# SensadoCalibradoMaquinas.net
KiCad netlist of a schematic drawn in EAGLE
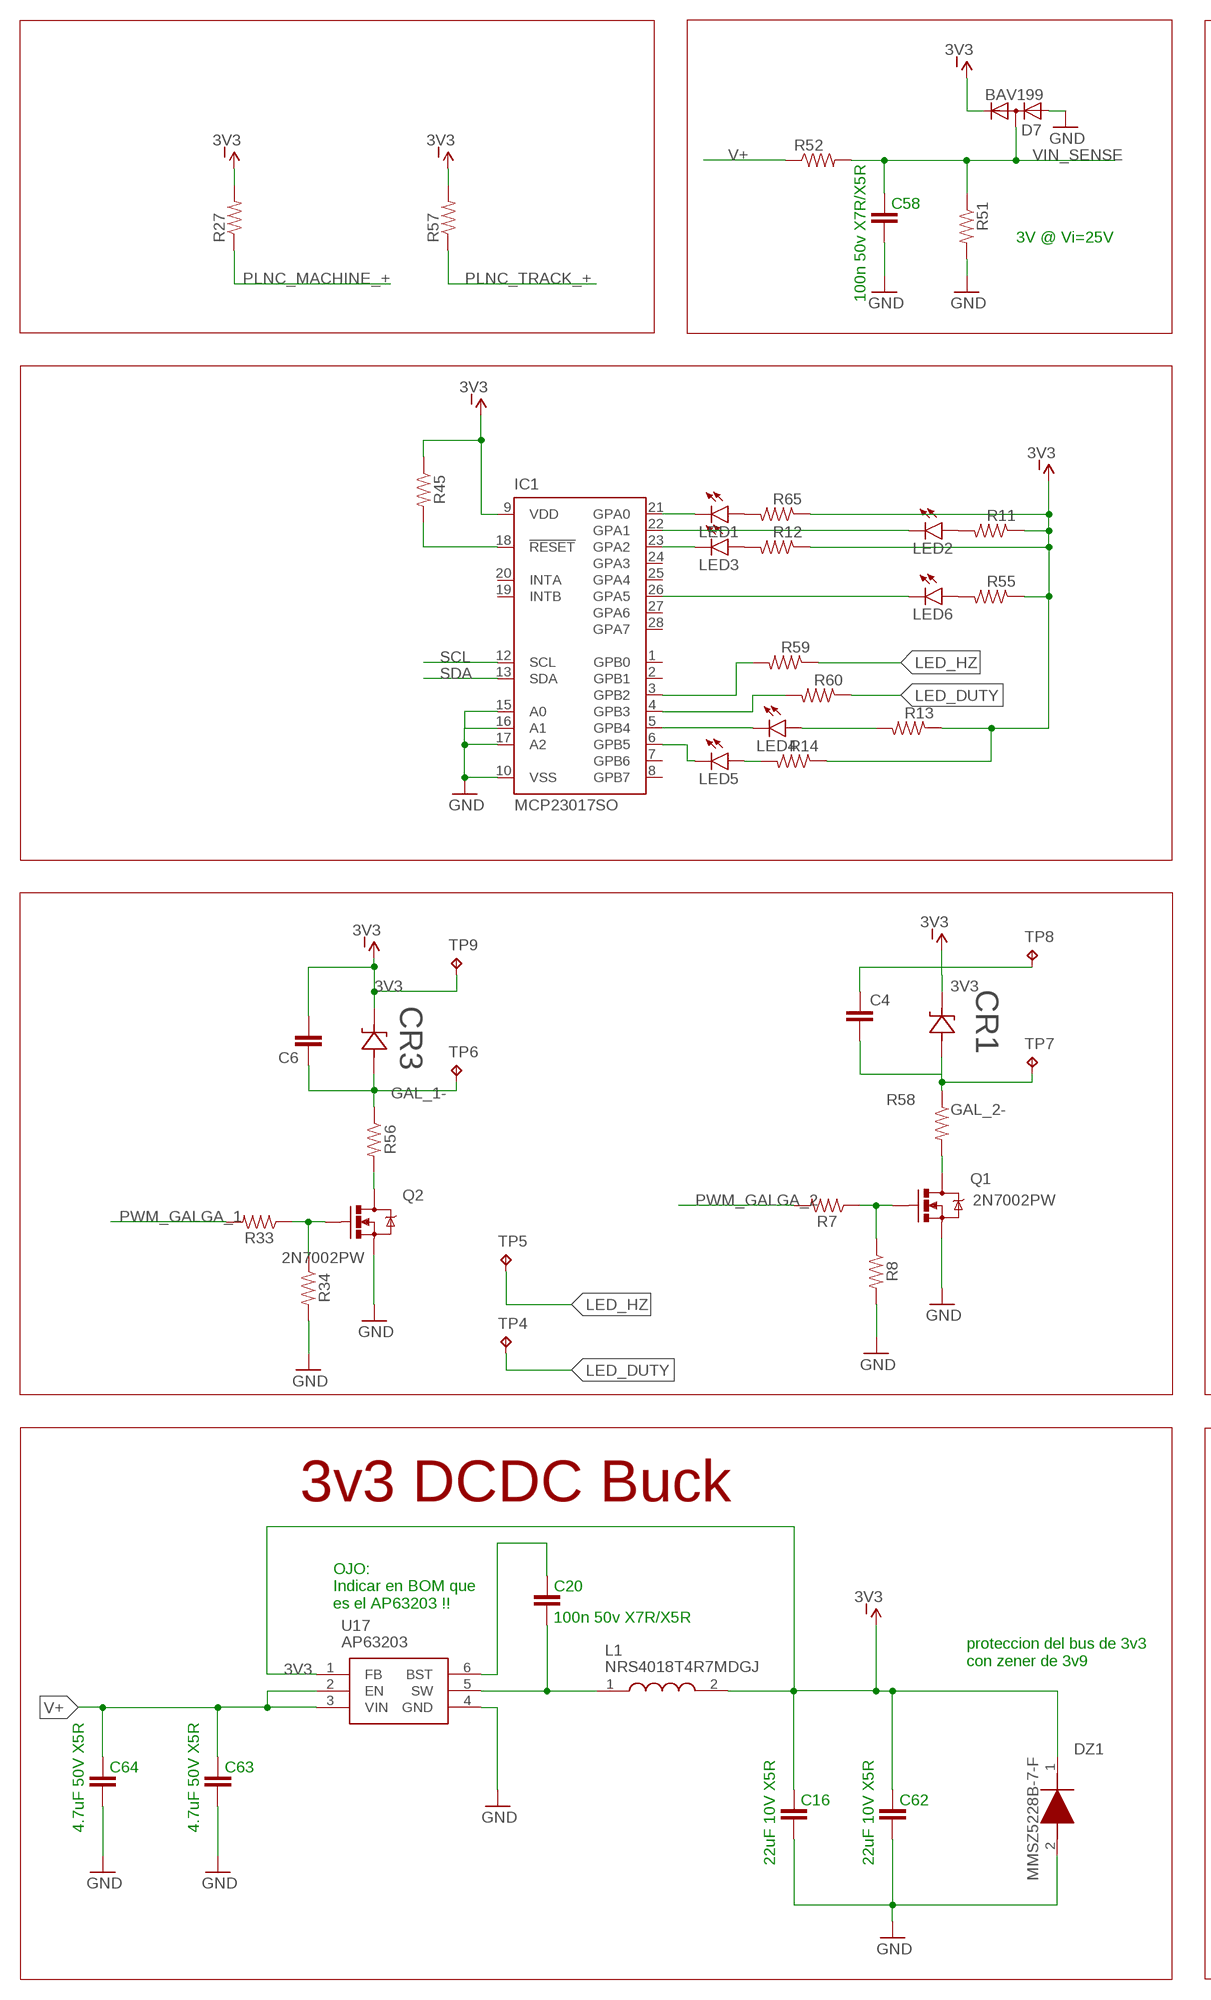
[diagram p0: schematic, sheet 1, part 1 of 2]
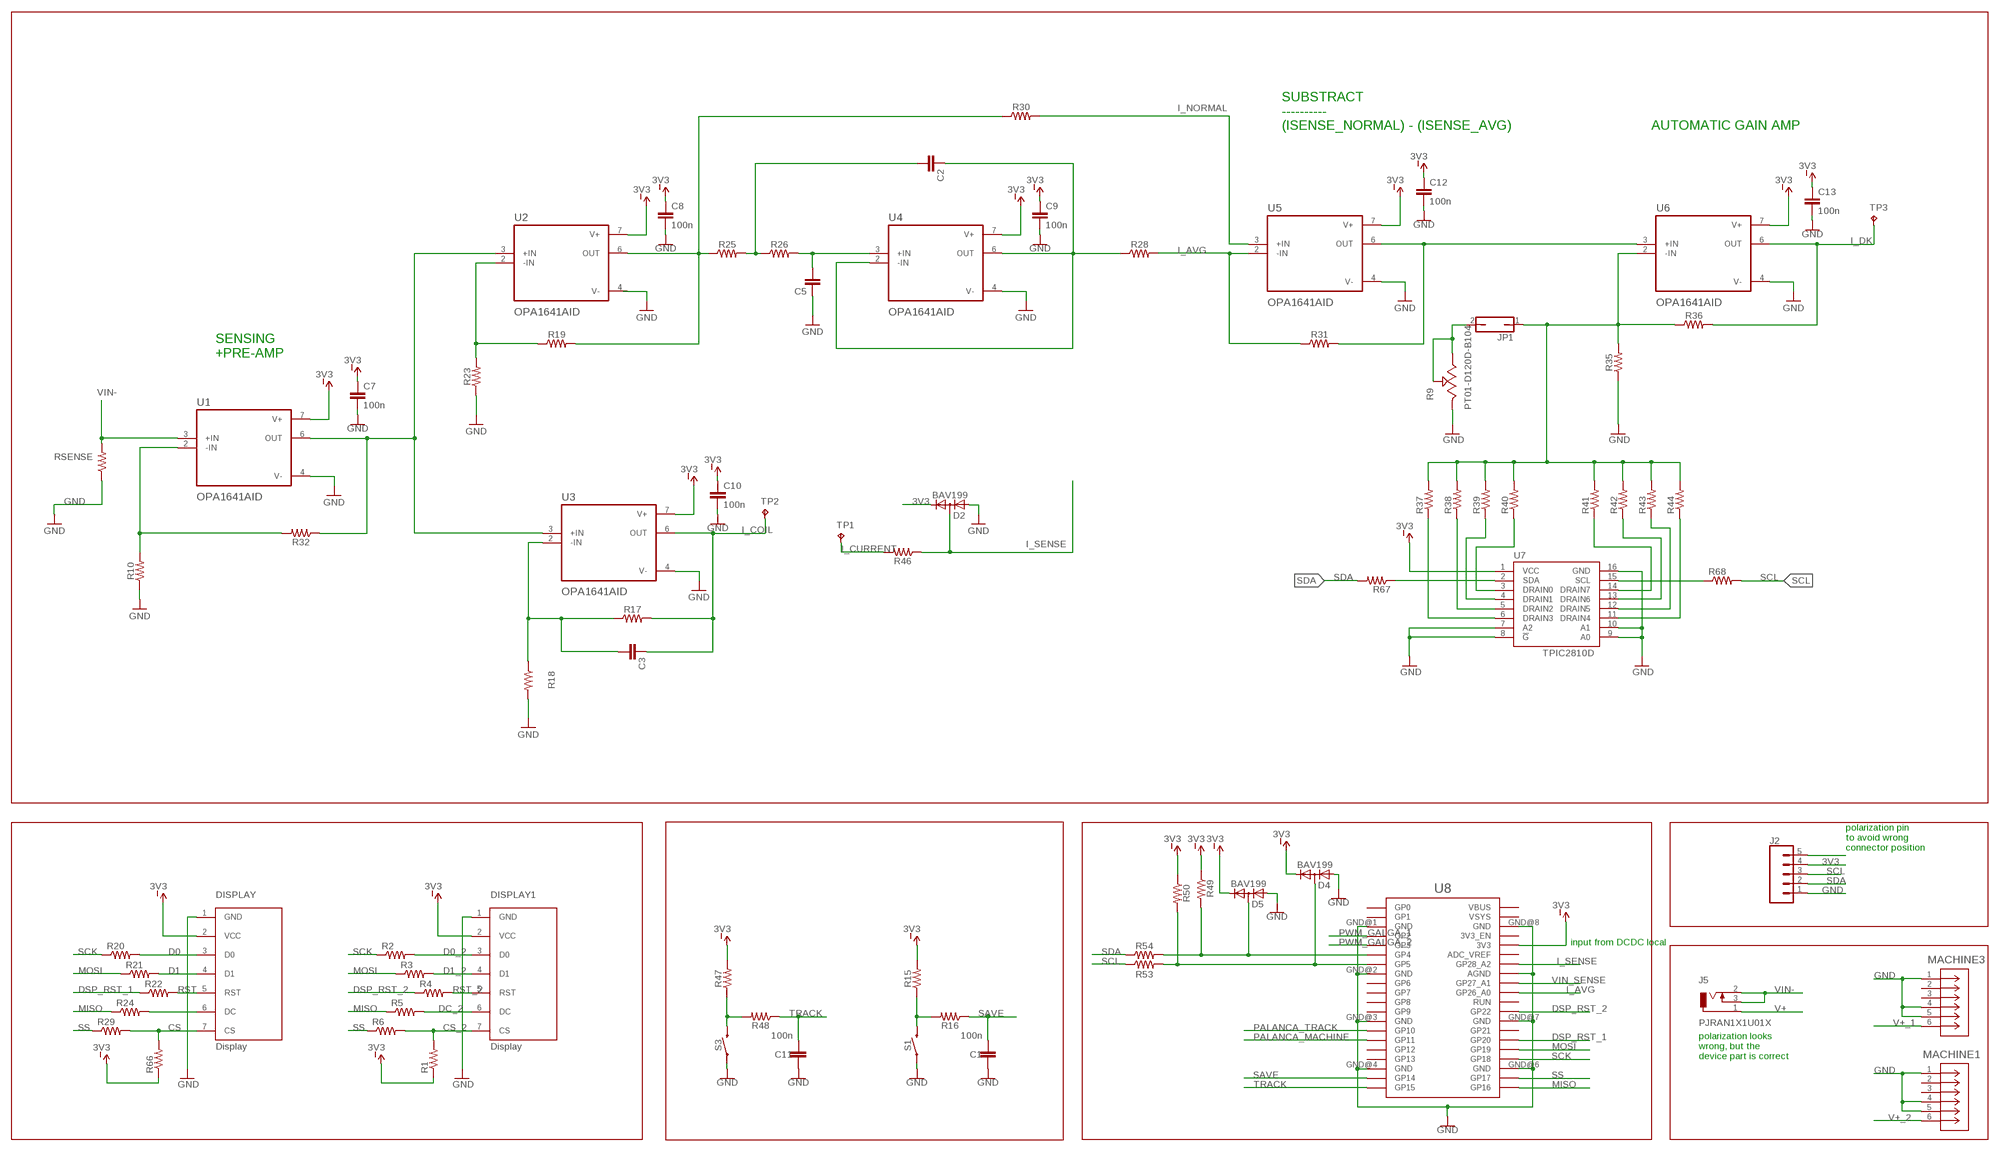
[diagram p1: schematic, sheet 1, part 2 of 2]

(export (version "E")
  (design (tool "Eeschema 10.0.6"))
  (components
    (comp (ref "C1")
      (value "100n")
      (footprint "eagle-import:0805")
      (libsource (lib "eagle-import") (part "1.0UF-0805-25V-(+80/-20%)"))
    )
    (comp (ref "C2")
      (value "CAP0805")
      (footprint "eagle-import:0805")
      (libsource (lib "eagle-import") (part "CAP0805"))
    )
    (comp (ref "C3")
      (value "CAP0805")
      (footprint "eagle-import:0805")
      (libsource (lib "eagle-import") (part "CAP0805"))
    )
    (comp (ref "C4")
      (value "CAP0805")
      (footprint "eagle-import:0805")
      (libsource (lib "eagle-import") (part "CAP0805"))
    )
    (comp (ref "C5")
      (value "CAP0805")
      (footprint "eagle-import:0805")
      (libsource (lib "eagle-import") (part "CAP0805"))
    )
    (comp (ref "C6")
      (value "CAP0805")
      (footprint "eagle-import:0805")
      (libsource (lib "eagle-import") (part "CAP0805"))
    )
    (comp (ref "C7")
      (value "100n")
      (footprint "eagle-import:0805")
      (libsource (lib "eagle-import") (part "1.0UF-0805-25V-(+80/-20%)"))
    )
    (comp (ref "C8")
      (value "100n")
      (footprint "eagle-import:0805")
      (libsource (lib "eagle-import") (part "1.0UF-0805-25V-(+80/-20%)"))
    )
    (comp (ref "C9")
      (value "100n")
      (footprint "eagle-import:0805")
      (libsource (lib "eagle-import") (part "1.0UF-0805-25V-(+80/-20%)"))
    )
    (comp (ref "C10")
      (value "100n")
      (footprint "eagle-import:0805")
      (libsource (lib "eagle-import") (part "1.0UF-0805-25V-(+80/-20%)"))
    )
    (comp (ref "C11")
      (value "100n")
      (footprint "eagle-import:0805")
      (libsource (lib "eagle-import") (part "1.0UF-0805-25V-(+80/-20%)"))
    )
    (comp (ref "C12")
      (value "100n")
      (footprint "eagle-import:0805")
      (libsource (lib "eagle-import") (part "1.0UF-0805-25V-(+80/-20%)"))
    )
    (comp (ref "C13")
      (value "100n")
      (footprint "eagle-import:0805")
      (libsource (lib "eagle-import") (part "1.0UF-0805-25V-(+80/-20%)"))
    )
    (comp (ref "C16")
      (value "22uF 10V X5R")
      (footprint "eagle-import:0805")
      (libsource (lib "eagle-import") (part "CAP0805"))
    )
    (comp (ref "C20")
      (value "100n 50v X7R/X5R")
      (footprint "eagle-import:0805")
      (libsource (lib "eagle-import") (part "CAP0805"))
    )
    (comp (ref "C58")
      (value "100n 50v X7R/X5R")
      (footprint "eagle-import:0805")
      (libsource (lib "eagle-import") (part "CAP0805"))
    )
    (comp (ref "C62")
      (value "22uF 10V X5R")
      (footprint "eagle-import:0805")
      (libsource (lib "eagle-import") (part "CAP0805"))
    )
    (comp (ref "C63")
      (value "4.7uF 50V X5R")
      (footprint "eagle-import:0805")
      (libsource (lib "eagle-import") (part "CAP0805"))
    )
    (comp (ref "C64")
      (value "4.7uF 50V X5R")
      (footprint "eagle-import:0805")
      (libsource (lib "eagle-import") (part "CAP0805"))
    )
    (comp (ref "CR1")
      (value "STPS1L40U")
      (footprint "eagle-import:SMB_STM")
      (fields (field (name "COPYRIGHT") "Copyright (C) 2024 Ultra Librarian. All rights reserved."))
      (libsource (lib "eagle-import") (part "STPS1L40U"))
    )
    (comp (ref "CR3")
      (value "STPS1L40U")
      (footprint "eagle-import:SMB_STM")
      (fields (field (name "COPYRIGHT") "Copyright (C) 2024 Ultra Librarian. All rights reserved."))
      (libsource (lib "eagle-import") (part "STPS1L40U"))
    )
    (comp (ref "D2")
      (value "BAV199")
      (footprint "eagle-import:SOT23")
      (libsource (lib "eagle-import") (part "BAV199"))
    )
    (comp (ref "D4")
      (value "BAV199")
      (footprint "eagle-import:SOT23")
      (libsource (lib "eagle-import") (part "BAV199"))
    )
    (comp (ref "D5")
      (value "BAV199")
      (footprint "eagle-import:SOT23")
      (libsource (lib "eagle-import") (part "BAV199"))
    )
    (comp (ref "D7")
      (value "BAV199")
      (footprint "eagle-import:SOT23")
      (libsource (lib "eagle-import") (part "BAV199"))
    )
    (comp (ref "DISPLAY")
      (value "Display")
      (footprint "eagle-import:OLED_LCD")
      (libsource (lib "eagle-import") (part "OLED_LCD"))
    )
    (comp (ref "DISPLAY1")
      (value "Display")
      (footprint "eagle-import:OLED_LCD")
      (libsource (lib "eagle-import") (part "OLED_LCD"))
    )
    (comp (ref "DZ1")
      (value "MMSZ5228B-7-F")
      (footprint "eagle-import:SODFL3518X115N")
      (libsource (lib "eagle-import") (part "MMSZ5228B-7-F"))
    )
    (comp (ref "IC1")
      (value "MCP23017SO")
      (footprint "eagle-import:SO28W")
      (libsource (lib "eagle-import") (part "MCP23017SO"))
    )
    (comp (ref "J2")
      (value "CONN_05")
      (footprint "eagle-import:1X05")
      (libsource (lib "eagle-import") (part "CONN_05"))
    )
    (comp (ref "J5")
      (value "PJRAN1X1U01X")
      (footprint "eagle-import:PJRAN1X1U01X")
      (fields
        (field (name "DIGIKEY_PART_NUMBER") "PJRAN1X1U01X-ND")
        (field (name "MANUFACTURER") "Switchcraft Inc.")
        (field (name "CREATED_BY") "PCBLayout.com")
      )
      (libsource (lib "eagle-import") (part "PJRAN1X1U01X"))
    )
    (comp (ref "JP1")
      (value "JP1Q")
      (footprint "eagle-import:JP1")
      (libsource (lib "eagle-import") (part "JP1Q"))
    )
    (comp (ref "L1")
      (value "NRS4018T4R7MDGJ")
      (footprint "eagle-import:NRS4018T100MDGJ")
      (fields (field (name "MOUSER_PART_NUMBER") "963-NRS4018T4R7MDGJ"))
      (libsource (lib "eagle-import") (part "NRS4018T4R7MDGJ"))
    )
    (comp (ref "LED1")
      (value "LED3MM")
      (footprint "eagle-import:LED3MM")
      (libsource (lib "eagle-import") (part "LED3MM"))
    )
    (comp (ref "LED2")
      (value "LED3MM")
      (footprint "eagle-import:LED3MM")
      (libsource (lib "eagle-import") (part "LED3MM"))
    )
    (comp (ref "LED3")
      (value "LED3MM")
      (footprint "eagle-import:LED3MM")
      (libsource (lib "eagle-import") (part "LED3MM"))
    )
    (comp (ref "LED4")
      (value "LED3MM")
      (footprint "eagle-import:LED3MM")
      (libsource (lib "eagle-import") (part "LED3MM"))
    )
    (comp (ref "LED5")
      (value "LED3MM")
      (footprint "eagle-import:LED3MM")
      (libsource (lib "eagle-import") (part "LED3MM"))
    )
    (comp (ref "LED6")
      (value "LED3MM")
      (footprint "eagle-import:LED3MM")
      (libsource (lib "eagle-import") (part "LED3MM"))
    )
    (comp (ref "MACHINE1")
      (value "ACJS-MHDR")
      (footprint "eagle-import:CONN_MHDR_AMP")
      (fields (field (name "COPYRIGHT") "Copyright (C) 2018 Accelerated Designs. All rights reserved"))
      (libsource (lib "eagle-import") (part "ACJS-MHDR"))
    )
    (comp (ref "MACHINE3")
      (value "ACJS-MHDR")
      (footprint "eagle-import:CONN_MHDR_AMP")
      (fields (field (name "COPYRIGHT") "Copyright (C) 2018 Accelerated Designs. All rights reserved"))
      (libsource (lib "eagle-import") (part "ACJS-MHDR"))
    )
    (comp (ref "Q1")
      (value "2N7002PW")
      (footprint "eagle-import:SOT323")
      (libsource (lib "eagle-import") (part "MOSFET-NCHANNEL2N7002PW"))
    )
    (comp (ref "Q2")
      (value "2N7002PW")
      (footprint "eagle-import:SOT323")
      (libsource (lib "eagle-import") (part "MOSFET-NCHANNEL2N7002PW"))
    )
    (comp (ref "R1")
      (value "RESISTOR0805")
      (footprint "eagle-import:0805")
      (libsource (lib "eagle-import") (part "RESISTOR0805"))
    )
    (comp (ref "R2")
      (value "RESISTOR0805")
      (footprint "eagle-import:0805")
      (libsource (lib "eagle-import") (part "RESISTOR0805"))
    )
    (comp (ref "R3")
      (value "RESISTOR0805")
      (footprint "eagle-import:0805")
      (libsource (lib "eagle-import") (part "RESISTOR0805"))
    )
    (comp (ref "R4")
      (value "RESISTOR0805")
      (footprint "eagle-import:0805")
      (libsource (lib "eagle-import") (part "RESISTOR0805"))
    )
    (comp (ref "R5")
      (value "RESISTOR0805")
      (footprint "eagle-import:0805")
      (libsource (lib "eagle-import") (part "RESISTOR0805"))
    )
    (comp (ref "R6")
      (value "RESISTOR0805")
      (footprint "eagle-import:0805")
      (libsource (lib "eagle-import") (part "RESISTOR0805"))
    )
    (comp (ref "R7")
      (value "RESISTOR0805")
      (footprint "eagle-import:0805")
      (libsource (lib "eagle-import") (part "RESISTOR0805"))
    )
    (comp (ref "R8")
      (value "RESISTOR0805")
      (footprint "eagle-import:0805")
      (libsource (lib "eagle-import") (part "RESISTOR0805"))
    )
    (comp (ref "R9")
      (value "PT01-D120D-B104")
      (footprint "eagle-import:TRIM_PT01-D120D-B104")
      (fields (field (name "MANUFACTURER") "CUI Devices"))
      (libsource (lib "eagle-import") (part "PT01-D120D-B104"))
    )
    (comp (ref "R10")
      (value "RESISTOR0805")
      (footprint "eagle-import:0805")
      (libsource (lib "eagle-import") (part "RESISTOR0805"))
    )
    (comp (ref "R11")
      (value "RESISTOR0805")
      (footprint "eagle-import:0805")
      (libsource (lib "eagle-import") (part "RESISTOR0805"))
    )
    (comp (ref "R12")
      (value "RESISTOR0805")
      (footprint "eagle-import:0805")
      (libsource (lib "eagle-import") (part "RESISTOR0805"))
    )
    (comp (ref "R13")
      (value "RESISTOR0805")
      (footprint "eagle-import:0805")
      (libsource (lib "eagle-import") (part "RESISTOR0805"))
    )
    (comp (ref "R14")
      (value "RESISTOR0805")
      (footprint "eagle-import:0805")
      (libsource (lib "eagle-import") (part "RESISTOR0805"))
    )
    (comp (ref "R15")
      (value "RESISTOR0805")
      (footprint "eagle-import:0805")
      (libsource (lib "eagle-import") (part "RESISTOR0805"))
    )
    (comp (ref "R16")
      (value "RESISTOR0805")
      (footprint "eagle-import:0805")
      (libsource (lib "eagle-import") (part "RESISTOR0805"))
    )
    (comp (ref "R17")
      (value "RESISTOR0805")
      (footprint "eagle-import:0805")
      (libsource (lib "eagle-import") (part "RESISTOR0805"))
    )
    (comp (ref "R18")
      (value "RESISTOR0805")
      (footprint "eagle-import:0805")
      (libsource (lib "eagle-import") (part "RESISTOR0805"))
    )
    (comp (ref "R19")
      (value "RESISTOR0805")
      (footprint "eagle-import:0805")
      (libsource (lib "eagle-import") (part "RESISTOR0805"))
    )
    (comp (ref "R20")
      (value "RESISTOR0805")
      (footprint "eagle-import:0805")
      (libsource (lib "eagle-import") (part "RESISTOR0805"))
    )
    (comp (ref "R21")
      (value "RESISTOR0805")
      (footprint "eagle-import:0805")
      (libsource (lib "eagle-import") (part "RESISTOR0805"))
    )
    (comp (ref "R22")
      (value "RESISTOR0805")
      (footprint "eagle-import:0805")
      (libsource (lib "eagle-import") (part "RESISTOR0805"))
    )
    (comp (ref "R23")
      (value "RESISTOR0805")
      (footprint "eagle-import:0805")
      (libsource (lib "eagle-import") (part "RESISTOR0805"))
    )
    (comp (ref "R24")
      (value "RESISTOR0805")
      (footprint "eagle-import:0805")
      (libsource (lib "eagle-import") (part "RESISTOR0805"))
    )
    (comp (ref "R25")
      (value "RESISTOR0805")
      (footprint "eagle-import:0805")
      (libsource (lib "eagle-import") (part "RESISTOR0805"))
    )
    (comp (ref "R26")
      (value "RESISTOR0805")
      (footprint "eagle-import:0805")
      (libsource (lib "eagle-import") (part "RESISTOR0805"))
    )
    (comp (ref "R27")
      (value "RESISTOR0805")
      (footprint "eagle-import:0805")
      (libsource (lib "eagle-import") (part "RESISTOR0805"))
    )
    (comp (ref "R28")
      (value "RESISTOR0805")
      (footprint "eagle-import:0805")
      (libsource (lib "eagle-import") (part "RESISTOR0805"))
    )
    (comp (ref "R29")
      (value "RESISTOR0805")
      (footprint "eagle-import:0805")
      (libsource (lib "eagle-import") (part "RESISTOR0805"))
    )
    (comp (ref "R30")
      (value "RESISTOR0805")
      (footprint "eagle-import:0805")
      (libsource (lib "eagle-import") (part "RESISTOR0805"))
    )
    (comp (ref "R31")
      (value "RESISTOR0805")
      (footprint "eagle-import:0805")
      (libsource (lib "eagle-import") (part "RESISTOR0805"))
    )
    (comp (ref "R32")
      (value "RESISTOR0805")
      (footprint "eagle-import:0805")
      (libsource (lib "eagle-import") (part "RESISTOR0805"))
    )
    (comp (ref "R33")
      (value "RESISTOR0805")
      (footprint "eagle-import:0805")
      (libsource (lib "eagle-import") (part "RESISTOR0805"))
    )
    (comp (ref "R34")
      (value "RESISTOR0805")
      (footprint "eagle-import:0805")
      (libsource (lib "eagle-import") (part "RESISTOR0805"))
    )
    (comp (ref "R35")
      (value "RESISTOR0805")
      (footprint "eagle-import:0805")
      (libsource (lib "eagle-import") (part "RESISTOR0805"))
    )
    (comp (ref "R36")
      (value "RESISTOR0805")
      (footprint "eagle-import:0805")
      (libsource (lib "eagle-import") (part "RESISTOR0805"))
    )
    (comp (ref "R37")
      (value "RESISTOR0805")
      (footprint "eagle-import:0805")
      (libsource (lib "eagle-import") (part "RESISTOR0805"))
    )
    (comp (ref "R38")
      (value "RESISTOR0805")
      (footprint "eagle-import:0805")
      (libsource (lib "eagle-import") (part "RESISTOR0805"))
    )
    (comp (ref "R39")
      (value "RESISTOR0805")
      (footprint "eagle-import:0805")
      (libsource (lib "eagle-import") (part "RESISTOR0805"))
    )
    (comp (ref "R40")
      (value "RESISTOR0805")
      (footprint "eagle-import:0805")
      (libsource (lib "eagle-import") (part "RESISTOR0805"))
    )
    (comp (ref "R41")
      (value "RESISTOR0805")
      (footprint "eagle-import:0805")
      (libsource (lib "eagle-import") (part "RESISTOR0805"))
    )
    (comp (ref "R42")
      (value "RESISTOR0805")
      (footprint "eagle-import:0805")
      (libsource (lib "eagle-import") (part "RESISTOR0805"))
    )
    (comp (ref "R43")
      (value "RESISTOR0805")
      (footprint "eagle-import:0805")
      (libsource (lib "eagle-import") (part "RESISTOR0805"))
    )
    (comp (ref "R44")
      (value "RESISTOR0805")
      (footprint "eagle-import:0805")
      (libsource (lib "eagle-import") (part "RESISTOR0805"))
    )
    (comp (ref "R45")
      (value "RESISTOR0805")
      (footprint "eagle-import:0805")
      (libsource (lib "eagle-import") (part "RESISTOR0805"))
    )
    (comp (ref "R46")
      (value "RESISTOR0805")
      (footprint "eagle-import:0805")
      (libsource (lib "eagle-import") (part "RESISTOR0805"))
    )
    (comp (ref "R47")
      (value "RESISTOR0805")
      (footprint "eagle-import:0805")
      (libsource (lib "eagle-import") (part "RESISTOR0805"))
    )
    (comp (ref "R48")
      (value "RESISTOR0805")
      (footprint "eagle-import:0805")
      (libsource (lib "eagle-import") (part "RESISTOR0805"))
    )
    (comp (ref "R49")
      (value "RESISTOR0805")
      (footprint "eagle-import:0805")
      (libsource (lib "eagle-import") (part "RESISTOR0805"))
    )
    (comp (ref "R50")
      (value "RESISTOR0805")
      (footprint "eagle-import:0805")
      (libsource (lib "eagle-import") (part "RESISTOR0805"))
    )
    (comp (ref "R51")
      (value "RESISTOR0805")
      (footprint "eagle-import:0805")
      (libsource (lib "eagle-import") (part "RESISTOR0805"))
    )
    (comp (ref "R52")
      (value "RESISTOR0805")
      (footprint "eagle-import:0805")
      (libsource (lib "eagle-import") (part "RESISTOR0805"))
    )
    (comp (ref "R53")
      (value "RESISTOR0805")
      (footprint "eagle-import:0805")
      (libsource (lib "eagle-import") (part "RESISTOR0805"))
    )
    (comp (ref "R54")
      (value "RESISTOR0805")
      (footprint "eagle-import:0805")
      (libsource (lib "eagle-import") (part "RESISTOR0805"))
    )
    (comp (ref "R55")
      (value "RESISTOR0805")
      (footprint "eagle-import:0805")
      (libsource (lib "eagle-import") (part "RESISTOR0805"))
    )
    (comp (ref "R56")
      (value "RESISTOR0805")
      (footprint "eagle-import:0805")
      (libsource (lib "eagle-import") (part "RESISTOR0805"))
    )
    (comp (ref "R57")
      (value "RESISTOR0805")
      (footprint "eagle-import:0805")
      (libsource (lib "eagle-import") (part "RESISTOR0805"))
    )
    (comp (ref "R58")
      (value "RESISTOR0805")
      (footprint "eagle-import:0805")
      (libsource (lib "eagle-import") (part "RESISTOR0805"))
    )
    (comp (ref "R59")
      (value "RESISTOR0805")
      (footprint "eagle-import:0805")
      (libsource (lib "eagle-import") (part "RESISTOR0805"))
    )
    (comp (ref "R60")
      (value "RESISTOR0805")
      (footprint "eagle-import:0805")
      (libsource (lib "eagle-import") (part "RESISTOR0805"))
    )
    (comp (ref "R65")
      (value "RESISTOR0805")
      (footprint "eagle-import:0805")
      (libsource (lib "eagle-import") (part "RESISTOR0805"))
    )
    (comp (ref "R66")
      (value "RESISTOR0805")
      (footprint "eagle-import:0805")
      (libsource (lib "eagle-import") (part "RESISTOR0805"))
    )
    (comp (ref "R67")
      (value "RESISTOR0805")
      (footprint "eagle-import:0805")
      (libsource (lib "eagle-import") (part "RESISTOR0805"))
    )
    (comp (ref "R68")
      (value "RESISTOR0805")
      (footprint "eagle-import:0805")
      (libsource (lib "eagle-import") (part "RESISTOR0805"))
    )
    (comp (ref "RSENSE")
      (value "RESISTORAXIAL-0.3")
      (footprint "eagle-import:AXIAL-0.3")
      (libsource (lib "eagle-import") (part "RESISTORAXIAL-0.3"))
    )
    (comp (ref "S1")
      (value "MOMENTARY-SWITCH-SPST-SMD-5.2MM")
      (footprint "eagle-import:TACTILE_SWITCH_SMD_5.2MM")
      (libsource (lib "eagle-import") (part "MOMENTARY-SWITCH-SPST-SMD-5.2MM"))
    )
    (comp (ref "S3")
      (value "MOMENTARY-SWITCH-SPST-SMD-5.2MM")
      (footprint "eagle-import:TACTILE_SWITCH_SMD_5.2MM")
      (libsource (lib "eagle-import") (part "MOMENTARY-SWITCH-SPST-SMD-5.2MM"))
    )
    (comp (ref "TP1")
      (value "TPTP06SQ")
      (footprint "eagle-import:TP06SQ")
      (libsource (lib "eagle-import") (part "TPTP06SQ"))
    )
    (comp (ref "TP2")
      (value "TPTP06SQ")
      (footprint "eagle-import:TP06SQ")
      (libsource (lib "eagle-import") (part "TPTP06SQ"))
    )
    (comp (ref "TP3")
      (value "TPTP06SQ")
      (footprint "eagle-import:TP06SQ")
      (libsource (lib "eagle-import") (part "TPTP06SQ"))
    )
    (comp (ref "TP4")
      (value "TPTP06SQ")
      (footprint "eagle-import:TP06SQ")
      (libsource (lib "eagle-import") (part "TPTP06SQ"))
    )
    (comp (ref "TP5")
      (value "TPTP06SQ")
      (footprint "eagle-import:TP06SQ")
      (libsource (lib "eagle-import") (part "TPTP06SQ"))
    )
    (comp (ref "TP6")
      (value "TPTP06SQ")
      (footprint "eagle-import:TP06SQ")
      (libsource (lib "eagle-import") (part "TPTP06SQ"))
    )
    (comp (ref "TP7")
      (value "TPTP06SQ")
      (footprint "eagle-import:TP06SQ")
      (libsource (lib "eagle-import") (part "TPTP06SQ"))
    )
    (comp (ref "TP8")
      (value "TPTP06SQ")
      (footprint "eagle-import:TP06SQ")
      (libsource (lib "eagle-import") (part "TPTP06SQ"))
    )
    (comp (ref "TP9")
      (value "TPTP06SQ")
      (footprint "eagle-import:TP06SQ")
      (libsource (lib "eagle-import") (part "TPTP06SQ"))
    )
    (comp (ref "U1")
      (value "OPA1641AID")
      (footprint "eagle-import:SOIC127P599X175-8N")
      (libsource (lib "eagle-import") (part "OPA1641AID"))
    )
    (comp (ref "U2")
      (value "OPA1641AID")
      (footprint "eagle-import:SOIC127P599X175-8N")
      (libsource (lib "eagle-import") (part "OPA1641AID"))
    )
    (comp (ref "U3")
      (value "OPA1641AID")
      (footprint "eagle-import:SOIC127P599X175-8N")
      (libsource (lib "eagle-import") (part "OPA1641AID"))
    )
    (comp (ref "U4")
      (value "OPA1641AID")
      (footprint "eagle-import:SOIC127P599X175-8N")
      (libsource (lib "eagle-import") (part "OPA1641AID"))
    )
    (comp (ref "U5")
      (value "OPA1641AID")
      (footprint "eagle-import:SOIC127P599X175-8N")
      (libsource (lib "eagle-import") (part "OPA1641AID"))
    )
    (comp (ref "U6")
      (value "OPA1641AID")
      (footprint "eagle-import:SOIC127P599X175-8N")
      (libsource (lib "eagle-import") (part "OPA1641AID"))
    )
    (comp (ref "U7")
      (value "TPIC2810D")
      (footprint "eagle-import:SO16")
      (libsource (lib "eagle-import") (part "TPIC2810D"))
    )
    (comp (ref "U8")
      (value "RPI_PICO_IG-TH")
      (footprint "eagle-import:RPI_PICO_TH")
      (libsource (lib "eagle-import") (part "RPI_PICO_IG-TH"))
    )
    (comp (ref "U17")
      (value "AP63203")
      (footprint "eagle-import:SOT95P280X100-6N")
      (fields
        (field (name "ARROW_PART_NUMBER") "AP63201WU-7")
        (field (name "MOUSER_PART_NUMBER") "621-AP63201WU-7")
      )
      (libsource (lib "eagle-import") (part "AP63201WU-7"))
    )
  )
  (nets
    (net (code "1") (name "/CS") (class "Default")
      (node (ref "DISPLAY") (pin "7") (pinfunction "CS_7") (pintype "bidirectional"))
      (node (ref "R29") (pin "2") (pinfunction "2_2") (pintype "passive"))
      (node (ref "R66") (pin "2") (pinfunction "2_2") (pintype "passive"))
    )
    (net (code "2") (name "/CS_2") (class "Default")
      (node (ref "DISPLAY1") (pin "7") (pinfunction "CS_7") (pintype "bidirectional"))
      (node (ref "R1") (pin "2") (pinfunction "2_2") (pintype "passive"))
      (node (ref "R6") (pin "2") (pinfunction "2_2") (pintype "passive"))
    )
    (net (code "3") (name "/D0") (class "Default")
      (node (ref "DISPLAY") (pin "3") (pinfunction "D0_3") (pintype "bidirectional"))
      (node (ref "R20") (pin "2") (pinfunction "2_2") (pintype "passive"))
    )
    (net (code "4") (name "/D0_2") (class "Default")
      (node (ref "DISPLAY1") (pin "3") (pinfunction "D0_3") (pintype "bidirectional"))
      (node (ref "R2") (pin "2") (pinfunction "2_2") (pintype "passive"))
    )
    (net (code "5") (name "/D1") (class "Default")
      (node (ref "DISPLAY") (pin "4") (pinfunction "D1_4") (pintype "bidirectional"))
      (node (ref "R21") (pin "2") (pinfunction "2_2") (pintype "passive"))
    )
    (net (code "6") (name "/D1_2") (class "Default")
      (node (ref "DISPLAY1") (pin "4") (pinfunction "D1_4") (pintype "bidirectional"))
      (node (ref "R3") (pin "2") (pinfunction "2_2") (pintype "passive"))
    )
    (net (code "7") (name "/DC_2") (class "Default")
      (node (ref "DISPLAY1") (pin "6") (pinfunction "DC_6") (pintype "bidirectional"))
      (node (ref "R5") (pin "2") (pinfunction "2_2") (pintype "passive"))
    )
    (net (code "8") (name "/DSP_RST_1") (class "Default")
      (node (ref "R22") (pin "1") (pinfunction "1_1") (pintype "passive"))
      (node (ref "U8") (pin "GP20") (pinfunction "GP20_GP20") (pintype "bidirectional"))
    )
    (net (code "9") (name "/DSP_RST_2") (class "Default")
      (node (ref "R4") (pin "1") (pinfunction "1_1") (pintype "passive"))
      (node (ref "U8") (pin "GP22") (pinfunction "GP22_GP22") (pintype "bidirectional"))
    )
    (net (code "10") (name "/GAL_1-") (class "Default")
      (node (ref "C6") (pin "1") (pinfunction "1_1") (pintype "passive"))
      (node (ref "CR3") (pin "1") (pinfunction "1_1") (pintype "passive"))
      (node (ref "R56") (pin "1") (pinfunction "1_1") (pintype "passive"))
      (node (ref "TP6") (pin "TP") (pinfunction "TP_TP") (pintype "input"))
    )
    (net (code "11") (name "/GAL_2-") (class "Default")
      (node (ref "C4") (pin "2") (pinfunction "2_2") (pintype "passive"))
      (node (ref "CR1") (pin "1") (pinfunction "1_1") (pintype "passive"))
      (node (ref "R58") (pin "1") (pinfunction "1_1") (pintype "passive"))
      (node (ref "TP7") (pin "TP") (pinfunction "TP_TP") (pintype "input"))
    )
    (net (code "12") (name "/I_AVG") (class "Default")
      (node (ref "R28") (pin "2") (pinfunction "2_2") (pintype "passive"))
      (node (ref "R31") (pin "1") (pinfunction "1_1") (pintype "passive"))
      (node (ref "U5") (pin "2") (pinfunction "-IN_2") (pintype "input"))
      (node (ref "U8") (pin "GP26_A0") (pinfunction "GP26_A0_GP26_A0") (pintype "bidirectional"))
    )
    (net (code "13") (name "/I_COIL") (class "Default")
      (node (ref "C3") (pin "1") (pinfunction "1_1") (pintype "passive"))
      (node (ref "R17") (pin "2") (pinfunction "2_2") (pintype "passive"))
      (node (ref "TP2") (pin "TP") (pinfunction "TP_TP") (pintype "input"))
      (node (ref "U3") (pin "6") (pinfunction "OUT_6") (pintype "output"))
    )
    (net (code "14") (name "/I_CURRENT") (class "Default")
      (node (ref "R46") (pin "2") (pinfunction "2_2") (pintype "passive"))
      (node (ref "TP1") (pin "TP") (pinfunction "TP_TP") (pintype "input"))
    )
    (net (code "15") (name "/I_DK") (class "Default")
      (node (ref "R36") (pin "2") (pinfunction "2_2") (pintype "passive"))
      (node (ref "TP3") (pin "TP") (pinfunction "TP_TP") (pintype "input"))
      (node (ref "U6") (pin "6") (pinfunction "OUT_6") (pintype "output"))
    )
    (net (code "16") (name "/I_NORMAL") (class "Default")
      (node (ref "R30") (pin "2") (pinfunction "2_2") (pintype "passive"))
      (node (ref "U5") (pin "3") (pinfunction "+IN_3") (pintype "input"))
    )
    (net (code "17") (name "/I_SENSE") (class "Default")
      (node (ref "D2") (pin "3") (pinfunction "AC_3") (pintype "passive"))
      (node (ref "R46") (pin "1") (pinfunction "1_1") (pintype "passive"))
      (node (ref "U8") (pin "GP28_A2") (pinfunction "GP28_A2_GP28_A2") (pintype "bidirectional"))
    )
    (net (code "18") (name "/MISO") (class "Default")
      (node (ref "R24") (pin "1") (pinfunction "1_1") (pintype "passive"))
      (node (ref "R5") (pin "1") (pinfunction "1_1") (pintype "passive"))
      (node (ref "U8") (pin "GP16") (pinfunction "GP16_GP16") (pintype "bidirectional"))
    )
    (net (code "19") (name "/MOSI") (class "Default")
      (node (ref "R21") (pin "1") (pinfunction "1_1") (pintype "passive"))
      (node (ref "R3") (pin "1") (pinfunction "1_1") (pintype "passive"))
      (node (ref "U8") (pin "GP19") (pinfunction "GP19_GP19") (pintype "bidirectional"))
    )
    (net (code "20") (name "/PALANCA_MACHINE") (class "Default")
      (node (ref "U8") (pin "GP11") (pinfunction "GP11_GP11") (pintype "bidirectional"))
    )
    (net (code "21") (name "/PALANCA_TRACK") (class "Default")
      (node (ref "U8") (pin "GP10") (pinfunction "GP10_GP10") (pintype "bidirectional"))
    )
    (net (code "22") (name "/PLNC_MACHINE_+") (class "Default")
      (node (ref "R27") (pin "1") (pinfunction "1_1") (pintype "passive"))
    )
    (net (code "23") (name "/PLNC_TRACK_+") (class "Default")
      (node (ref "R57") (pin "1") (pinfunction "1_1") (pintype "passive"))
    )
    (net (code "24") (name "/PWM_GALGA_1") (class "Default")
      (node (ref "R33") (pin "2") (pinfunction "2_2") (pintype "passive"))
      (node (ref "U8") (pin "GP2") (pinfunction "GP2_GP2") (pintype "bidirectional"))
    )
    (net (code "25") (name "/PWM_GALGA_2") (class "Default")
      (node (ref "R7") (pin "2") (pinfunction "2_2") (pintype "passive"))
      (node (ref "U8") (pin "GP3") (pinfunction "GP3_GP3") (pintype "bidirectional"))
    )
    (net (code "26") (name "/RST") (class "Default")
      (node (ref "DISPLAY") (pin "5") (pinfunction "RST_5") (pintype "bidirectional"))
      (node (ref "R22") (pin "2") (pinfunction "2_2") (pintype "passive"))
    )
    (net (code "27") (name "/RST_2") (class "Default")
      (node (ref "DISPLAY1") (pin "5") (pinfunction "RST_5") (pintype "bidirectional"))
      (node (ref "R4") (pin "2") (pinfunction "2_2") (pintype "passive"))
    )
    (net (code "28") (name "/SAVE") (class "Default")
      (node (ref "C1") (pin "2") (pinfunction "2_2") (pintype "passive"))
      (node (ref "R16") (pin "1") (pinfunction "1_1") (pintype "passive"))
      (node (ref "U8") (pin "GP14") (pinfunction "GP14_GP14") (pintype "bidirectional"))
    )
    (net (code "29") (name "/SCK") (class "Default")
      (node (ref "R2") (pin "1") (pinfunction "1_1") (pintype "passive"))
      (node (ref "R20") (pin "1") (pinfunction "1_1") (pintype "passive"))
      (node (ref "U8") (pin "GP18") (pinfunction "GP18_GP18") (pintype "bidirectional"))
    )
    (net (code "30") (name "/SS") (class "Default")
      (node (ref "R29") (pin "1") (pinfunction "1_1") (pintype "passive"))
      (node (ref "R6") (pin "1") (pinfunction "1_1") (pintype "passive"))
      (node (ref "U8") (pin "GP17") (pinfunction "GP17_GP17") (pintype "bidirectional"))
    )
    (net (code "31") (name "/TRACK") (class "Default")
      (node (ref "C11") (pin "2") (pinfunction "2_2") (pintype "passive"))
      (node (ref "R48") (pin "1") (pinfunction "1_1") (pintype "passive"))
      (node (ref "U8") (pin "GP15") (pinfunction "GP15_GP15") (pintype "bidirectional"))
    )
    (net (code "32") (name "/V+_1") (class "Default")
      (node (ref "MACHINE3") (pin "6") (pinfunction "6_6") (pintype "passive"))
    )
    (net (code "33") (name "/V+_2") (class "Default")
      (node (ref "MACHINE1") (pin "6") (pinfunction "6_6") (pintype "passive"))
    )
    (net (code "34") (name "/VIN-") (class "Default")
      (node (ref "J5") (pin "2") (pinfunction "2_2") (pintype "passive"))
      (node (ref "J5") (pin "3") (pinfunction "3_3") (pintype "passive"))
      (node (ref "RSENSE") (pin "P$2") (pinfunction "2_P$2") (pintype "passive"))
      (node (ref "U1") (pin "3") (pinfunction "+IN_3") (pintype "input"))
    )
    (net (code "35") (name "/VIN_SENSE") (class "Default")
      (node (ref "C58") (pin "2") (pinfunction "2_2") (pintype "passive"))
      (node (ref "D7") (pin "3") (pinfunction "AC_3") (pintype "passive"))
      (node (ref "R51") (pin "1") (pinfunction "1_1") (pintype "passive"))
      (node (ref "R52") (pin "2") (pinfunction "2_2") (pintype "passive"))
      (node (ref "U8") (pin "GP27_A1") (pinfunction "GP27_A1_GP27_A1") (pintype "bidirectional"))
    )
    (net (code "36") (name "3V3") (class "Default")
      (node (ref "C10") (pin "2") (pinfunction "2_2") (pintype "passive"))
      (node (ref "C12") (pin "2") (pinfunction "2_2") (pintype "passive"))
      (node (ref "C13") (pin "2") (pinfunction "2_2") (pintype "passive"))
      (node (ref "C16") (pin "2") (pinfunction "2_2") (pintype "passive"))
      (node (ref "C4") (pin "1") (pinfunction "1_1") (pintype "passive"))
      (node (ref "C6") (pin "2") (pinfunction "2_2") (pintype "passive"))
      (node (ref "C62") (pin "2") (pinfunction "2_2") (pintype "passive"))
      (node (ref "C7") (pin "2") (pinfunction "2_2") (pintype "passive"))
      (node (ref "C8") (pin "2") (pinfunction "2_2") (pintype "passive"))
      (node (ref "C9") (pin "2") (pinfunction "2_2") (pintype "passive"))
      (node (ref "CR1") (pin "2") (pinfunction "2_2") (pintype "passive"))
      (node (ref "CR3") (pin "2") (pinfunction "2_2") (pintype "passive"))
      (node (ref "D2") (pin "2") (pinfunction "C_2") (pintype "passive"))
      (node (ref "D4") (pin "2") (pinfunction "C_2") (pintype "passive"))
      (node (ref "D5") (pin "2") (pinfunction "C_2") (pintype "passive"))
      (node (ref "D7") (pin "2") (pinfunction "C_2") (pintype "passive"))
      (node (ref "DISPLAY") (pin "2") (pinfunction "VCC_2") (pintype "bidirectional"))
      (node (ref "DISPLAY1") (pin "2") (pinfunction "VCC_2") (pintype "bidirectional"))
      (node (ref "DZ1") (pin "1") (pinfunction "K_1") (pintype "bidirectional"))
      (node (ref "IC1") (pin "9") (pinfunction "VDD_9") (pintype "power_in"))
      (node (ref "J2") (pin "4") (pinfunction "4_4") (pintype "passive"))
      (node (ref "L1") (pin "2") (pinfunction "2_2") (pintype "bidirectional"))
      (node (ref "R1") (pin "1") (pinfunction "1_1") (pintype "passive"))
      (node (ref "R11") (pin "1") (pinfunction "1_1") (pintype "passive"))
      (node (ref "R12") (pin "1") (pinfunction "1_1") (pintype "passive"))
      (node (ref "R13") (pin "1") (pinfunction "1_1") (pintype "passive"))
      (node (ref "R14") (pin "1") (pinfunction "1_1") (pintype "passive"))
      (node (ref "R15") (pin "2") (pinfunction "2_2") (pintype "passive"))
      (node (ref "R27") (pin "2") (pinfunction "2_2") (pintype "passive"))
      (node (ref "R45") (pin "1") (pinfunction "1_1") (pintype "passive"))
      (node (ref "R47") (pin "2") (pinfunction "2_2") (pintype "passive"))
      (node (ref "R49") (pin "1") (pinfunction "1_1") (pintype "passive"))
      (node (ref "R50") (pin "1") (pinfunction "1_1") (pintype "passive"))
      (node (ref "R55") (pin "1") (pinfunction "1_1") (pintype "passive"))
      (node (ref "R57") (pin "2") (pinfunction "2_2") (pintype "passive"))
      (node (ref "R65") (pin "1") (pinfunction "1_1") (pintype "passive"))
      (node (ref "R66") (pin "1") (pinfunction "1_1") (pintype "passive"))
      (node (ref "TP8") (pin "TP") (pinfunction "TP_TP") (pintype "input"))
      (node (ref "TP9") (pin "TP") (pinfunction "TP_TP") (pintype "input"))
      (node (ref "U1") (pin "7") (pinfunction "V+_7") (pintype "power_in"))
      (node (ref "U17") (pin "1") (pinfunction "FB_1") (pintype "bidirectional"))
      (node (ref "U2") (pin "7") (pinfunction "V+_7") (pintype "power_in"))
      (node (ref "U3") (pin "7") (pinfunction "V+_7") (pintype "power_in"))
      (node (ref "U4") (pin "7") (pinfunction "V+_7") (pintype "power_in"))
      (node (ref "U5") (pin "7") (pinfunction "V+_7") (pintype "power_in"))
      (node (ref "U6") (pin "7") (pinfunction "V+_7") (pintype "power_in"))
      (node (ref "U7") (pin "1") (pinfunction "VCC_1") (pintype "bidirectional"))
      (node (ref "U8") (pin "3V3") (pinfunction "3V3_3V3") (pintype "bidirectional"))
    )
    (net (code "37") (name "GND") (class "Default")
      (node (ref "C1") (pin "1") (pinfunction "1_1") (pintype "passive"))
      (node (ref "C10") (pin "1") (pinfunction "1_1") (pintype "passive"))
      (node (ref "C11") (pin "1") (pinfunction "1_1") (pintype "passive"))
      (node (ref "C12") (pin "1") (pinfunction "1_1") (pintype "passive"))
      (node (ref "C13") (pin "1") (pinfunction "1_1") (pintype "passive"))
      (node (ref "C16") (pin "1") (pinfunction "1_1") (pintype "passive"))
      (node (ref "C5") (pin "1") (pinfunction "1_1") (pintype "passive"))
      (node (ref "C58") (pin "1") (pinfunction "1_1") (pintype "passive"))
      (node (ref "C62") (pin "1") (pinfunction "1_1") (pintype "passive"))
      (node (ref "C63") (pin "1") (pinfunction "1_1") (pintype "passive"))
      (node (ref "C64") (pin "1") (pinfunction "1_1") (pintype "passive"))
      (node (ref "C7") (pin "1") (pinfunction "1_1") (pintype "passive"))
      (node (ref "C8") (pin "1") (pinfunction "1_1") (pintype "passive"))
      (node (ref "C9") (pin "1") (pinfunction "1_1") (pintype "passive"))
      (node (ref "D2") (pin "1") (pinfunction "A_1") (pintype "passive"))
      (node (ref "D4") (pin "1") (pinfunction "A_1") (pintype "passive"))
      (node (ref "D5") (pin "1") (pinfunction "A_1") (pintype "passive"))
      (node (ref "D7") (pin "1") (pinfunction "A_1") (pintype "passive"))
      (node (ref "DISPLAY") (pin "1") (pinfunction "GND_1") (pintype "bidirectional"))
      (node (ref "DISPLAY1") (pin "1") (pinfunction "GND_1") (pintype "bidirectional"))
      (node (ref "DZ1") (pin "2") (pinfunction "A_2") (pintype "bidirectional"))
      (node (ref "IC1") (pin "10") (pinfunction "VSS_10") (pintype "power_in"))
      (node (ref "IC1") (pin "15") (pinfunction "A0_15") (pintype "input"))
      (node (ref "IC1") (pin "16") (pinfunction "A1_16") (pintype "input"))
      (node (ref "IC1") (pin "17") (pinfunction "A2_17") (pintype "input"))
      (node (ref "J2") (pin "1") (pinfunction "1_1") (pintype "passive"))
      (node (ref "MACHINE1") (pin "1") (pinfunction "1_1") (pintype "passive"))
      (node (ref "MACHINE1") (pin "4") (pinfunction "4_4") (pintype "passive"))
      (node (ref "MACHINE1") (pin "5") (pinfunction "5_5") (pintype "passive"))
      (node (ref "MACHINE3") (pin "1") (pinfunction "1_1") (pintype "passive"))
      (node (ref "MACHINE3") (pin "4") (pinfunction "4_4") (pintype "passive"))
      (node (ref "MACHINE3") (pin "5") (pinfunction "5_5") (pintype "passive"))
      (node (ref "Q1") (pin "2") (pinfunction "S_2") (pintype "passive"))
      (node (ref "Q2") (pin "2") (pinfunction "S_2") (pintype "passive"))
      (node (ref "R10") (pin "1") (pinfunction "1_1") (pintype "passive"))
      (node (ref "R18") (pin "2") (pinfunction "2_2") (pintype "passive"))
      (node (ref "R23") (pin "1") (pinfunction "1_1") (pintype "passive"))
      (node (ref "R34") (pin "2") (pinfunction "2_2") (pintype "passive"))
      (node (ref "R35") (pin "1") (pinfunction "1_1") (pintype "passive"))
      (node (ref "R51") (pin "2") (pinfunction "2_2") (pintype "passive"))
      (node (ref "R8") (pin "2") (pinfunction "2_2") (pintype "passive"))
      (node (ref "R9") (pin "1") (pinfunction "1_1") (pintype "passive"))
      (node (ref "RSENSE") (pin "P$1") (pinfunction "1_P$1") (pintype "passive"))
      (node (ref "S1") (pin "1") (pinfunction "1_1") (pintype "passive"))
      (node (ref "S3") (pin "1") (pinfunction "1_1") (pintype "passive"))
      (node (ref "U1") (pin "4") (pinfunction "V-_4") (pintype "power_in"))
      (node (ref "U17") (pin "4") (pinfunction "GND_4") (pintype "bidirectional"))
      (node (ref "U2") (pin "4") (pinfunction "V-_4") (pintype "power_in"))
      (node (ref "U3") (pin "4") (pinfunction "V-_4") (pintype "power_in"))
      (node (ref "U4") (pin "4") (pinfunction "V-_4") (pintype "power_in"))
      (node (ref "U5") (pin "4") (pinfunction "V-_4") (pintype "power_in"))
      (node (ref "U6") (pin "4") (pinfunction "V-_4") (pintype "power_in"))
      (node (ref "U7") (pin "10") (pinfunction "A1_10") (pintype "bidirectional"))
      (node (ref "U7") (pin "16") (pinfunction "GND_16") (pintype "bidirectional"))
      (node (ref "U7") (pin "7") (pinfunction "A2_7") (pintype "bidirectional"))
      (node (ref "U7") (pin "8") (pinfunction "~{G}_8") (pintype "bidirectional"))
      (node (ref "U7") (pin "9") (pinfunction "A0_9") (pintype "bidirectional"))
      (node (ref "U8") (pin "AGND") (pinfunction "AGND_AGND") (pintype "bidirectional"))
      (node (ref "U8") (pin "GND@1") (pinfunction "GND_GND@1") (pintype "bidirectional"))
      (node (ref "U8") (pin "GND@2") (pinfunction "GND_GND@2") (pintype "bidirectional"))
      (node (ref "U8") (pin "GND@3") (pinfunction "GND_GND@3") (pintype "bidirectional"))
      (node (ref "U8") (pin "GND@4") (pinfunction "GND_GND@4") (pintype "bidirectional"))
      (node (ref "U8") (pin "GND@6") (pinfunction "GND_GND@6") (pintype "bidirectional"))
      (node (ref "U8") (pin "GND@7") (pinfunction "GND_GND@7") (pintype "bidirectional"))
      (node (ref "U8") (pin "GND@8") (pinfunction "GND_GND@8") (pintype "bidirectional"))
    )
    (net (code "38") (name "LED_DUTY") (class "Default")
      (node (ref "R60") (pin "1") (pinfunction "1_1") (pintype "passive"))
      (node (ref "TP4") (pin "TP") (pinfunction "TP_TP") (pintype "input"))
    )
    (net (code "39") (name "LED_HZ") (class "Default")
      (node (ref "R59") (pin "1") (pinfunction "1_1") (pintype "passive"))
      (node (ref "TP5") (pin "TP") (pinfunction "TP_TP") (pintype "input"))
    )
    (net (code "40") (name "Net-(C2-Pad2)") (class "Default")
      (node (ref "C2") (pin "2") (pinfunction "2_2") (pintype "passive"))
      (node (ref "R25") (pin "2") (pinfunction "2_2") (pintype "passive"))
      (node (ref "R26") (pin "1") (pinfunction "1_1") (pintype "passive"))
    )
    (net (code "41") (name "Net-(D4-AC)") (class "Default")
      (node (ref "D4") (pin "3") (pinfunction "AC_3") (pintype "passive"))
      (node (ref "R50") (pin "2") (pinfunction "2_2") (pintype "passive"))
      (node (ref "R53") (pin "2") (pinfunction "2_2") (pintype "passive"))
      (node (ref "U8") (pin "GP5") (pinfunction "GP5_GP5") (pintype "bidirectional"))
    )
    (net (code "42") (name "Net-(D5-AC)") (class "Default")
      (node (ref "D5") (pin "3") (pinfunction "AC_3") (pintype "passive"))
      (node (ref "R49") (pin "2") (pinfunction "2_2") (pintype "passive"))
      (node (ref "R54") (pin "2") (pinfunction "2_2") (pintype "passive"))
      (node (ref "U8") (pin "GP4") (pinfunction "GP4_GP4") (pintype "bidirectional"))
    )
    (net (code "43") (name "Net-(DISPLAY-DC)") (class "Default")
      (node (ref "DISPLAY") (pin "6") (pinfunction "DC_6") (pintype "bidirectional"))
      (node (ref "R24") (pin "2") (pinfunction "2_2") (pintype "passive"))
    )
    (net (code "44") (name "Net-(IC1-GPA0)") (class "Default")
      (node (ref "IC1") (pin "21") (pinfunction "GPA0_21") (pintype "bidirectional"))
      (node (ref "LED1") (pin "K") (pinfunction "C_K") (pintype "passive"))
    )
    (net (code "45") (name "Net-(IC1-GPA1)") (class "Default")
      (node (ref "IC1") (pin "22") (pinfunction "GPA1_22") (pintype "bidirectional"))
      (node (ref "LED2") (pin "K") (pinfunction "C_K") (pintype "passive"))
    )
    (net (code "46") (name "Net-(IC1-GPA2)") (class "Default")
      (node (ref "IC1") (pin "23") (pinfunction "GPA2_23") (pintype "bidirectional"))
      (node (ref "LED3") (pin "K") (pinfunction "C_K") (pintype "passive"))
    )
    (net (code "47") (name "Net-(IC1-GPA5)") (class "Default")
      (node (ref "IC1") (pin "26") (pinfunction "GPA5_26") (pintype "bidirectional"))
      (node (ref "LED6") (pin "K") (pinfunction "C_K") (pintype "passive"))
    )
    (net (code "48") (name "Net-(IC1-GPB2)") (class "Default")
      (node (ref "IC1") (pin "3") (pinfunction "GPB2_3") (pintype "bidirectional"))
      (node (ref "R59") (pin "2") (pinfunction "2_2") (pintype "passive"))
    )
    (net (code "49") (name "Net-(IC1-GPB3)") (class "Default")
      (node (ref "IC1") (pin "4") (pinfunction "GPB3_4") (pintype "bidirectional"))
      (node (ref "R60") (pin "2") (pinfunction "2_2") (pintype "passive"))
    )
    (net (code "50") (name "Net-(IC1-GPB4)") (class "Default")
      (node (ref "IC1") (pin "5") (pinfunction "GPB4_5") (pintype "bidirectional"))
      (node (ref "LED4") (pin "K") (pinfunction "C_K") (pintype "passive"))
    )
    (net (code "51") (name "Net-(IC1-GPB5)") (class "Default")
      (node (ref "IC1") (pin "6") (pinfunction "GPB5_6") (pintype "bidirectional"))
      (node (ref "LED5") (pin "K") (pinfunction "C_K") (pintype "passive"))
    )
    (net (code "52") (name "Net-(IC1-~{RESET})") (class "Default")
      (node (ref "IC1") (pin "18") (pinfunction "~{RESET}_18") (pintype "input"))
      (node (ref "R45") (pin "2") (pinfunction "2_2") (pintype "passive"))
    )
    (net (code "53") (name "Net-(JP1-Pad2)") (class "Default")
      (node (ref "JP1") (pin "2") (pinfunction "2_2") (pintype "passive"))
      (node (ref "R9") (pin "2") (pinfunction "2_2") (pintype "passive"))
      (node (ref "R9") (pin "3") (pinfunction "3_3") (pintype "passive"))
    )
    (net (code "54") (name "Net-(LED1-PadA)") (class "Default")
      (node (ref "LED1") (pin "A") (pinfunction "A_A") (pintype "passive"))
      (node (ref "R65") (pin "2") (pinfunction "2_2") (pintype "passive"))
    )
    (net (code "55") (name "Net-(LED2-PadA)") (class "Default")
      (node (ref "LED2") (pin "A") (pinfunction "A_A") (pintype "passive"))
      (node (ref "R11") (pin "2") (pinfunction "2_2") (pintype "passive"))
    )
    (net (code "56") (name "Net-(LED3-PadA)") (class "Default")
      (node (ref "LED3") (pin "A") (pinfunction "A_A") (pintype "passive"))
      (node (ref "R12") (pin "2") (pinfunction "2_2") (pintype "passive"))
    )
    (net (code "57") (name "Net-(LED4-PadA)") (class "Default")
      (node (ref "LED4") (pin "A") (pinfunction "A_A") (pintype "passive"))
      (node (ref "R13") (pin "2") (pinfunction "2_2") (pintype "passive"))
    )
    (net (code "58") (name "Net-(LED5-PadA)") (class "Default")
      (node (ref "LED5") (pin "A") (pinfunction "A_A") (pintype "passive"))
      (node (ref "R14") (pin "2") (pinfunction "2_2") (pintype "passive"))
    )
    (net (code "59") (name "Net-(LED6-PadA)") (class "Default")
      (node (ref "LED6") (pin "A") (pinfunction "A_A") (pintype "passive"))
      (node (ref "R55") (pin "2") (pinfunction "2_2") (pintype "passive"))
    )
    (net (code "60") (name "Net-(Q1-D)") (class "Default")
      (node (ref "Q1") (pin "3") (pinfunction "D_3") (pintype "passive"))
      (node (ref "R58") (pin "2") (pinfunction "2_2") (pintype "passive"))
    )
    (net (code "61") (name "Net-(Q1-G)") (class "Default")
      (node (ref "Q1") (pin "1") (pinfunction "G_1") (pintype "passive"))
      (node (ref "R7") (pin "1") (pinfunction "1_1") (pintype "passive"))
      (node (ref "R8") (pin "1") (pinfunction "1_1") (pintype "passive"))
    )
    (net (code "62") (name "Net-(Q2-D)") (class "Default")
      (node (ref "Q2") (pin "3") (pinfunction "D_3") (pintype "passive"))
      (node (ref "R56") (pin "2") (pinfunction "2_2") (pintype "passive"))
    )
    (net (code "63") (name "Net-(Q2-G)") (class "Default")
      (node (ref "Q2") (pin "1") (pinfunction "G_1") (pintype "passive"))
      (node (ref "R33") (pin "1") (pinfunction "1_1") (pintype "passive"))
      (node (ref "R34") (pin "1") (pinfunction "1_1") (pintype "passive"))
    )
    (net (code "64") (name "Net-(S1-2)") (class "Default")
      (node (ref "R15") (pin "1") (pinfunction "1_1") (pintype "passive"))
      (node (ref "R16") (pin "2") (pinfunction "2_2") (pintype "passive"))
      (node (ref "S1") (pin "3") (pinfunction "2_3") (pintype "passive"))
    )
    (net (code "65") (name "Net-(S3-2)") (class "Default")
      (node (ref "R47") (pin "1") (pinfunction "1_1") (pintype "passive"))
      (node (ref "R48") (pin "2") (pinfunction "2_2") (pintype "passive"))
      (node (ref "S3") (pin "3") (pinfunction "2_3") (pintype "passive"))
    )
    (net (code "66") (name "Net-(U1--IN)") (class "Default")
      (node (ref "R10") (pin "2") (pinfunction "2_2") (pintype "passive"))
      (node (ref "R32") (pin "2") (pinfunction "2_2") (pintype "passive"))
      (node (ref "U1") (pin "2") (pinfunction "-IN_2") (pintype "input"))
    )
    (net (code "67") (name "Net-(U1-OUT)") (class "Default")
      (node (ref "R32") (pin "1") (pinfunction "1_1") (pintype "passive"))
      (node (ref "U1") (pin "6") (pinfunction "OUT_6") (pintype "output"))
      (node (ref "U2") (pin "3") (pinfunction "+IN_3") (pintype "input"))
      (node (ref "U3") (pin "3") (pinfunction "+IN_3") (pintype "input"))
    )
    (net (code "68") (name "Net-(U2--IN)") (class "Default")
      (node (ref "R19") (pin "1") (pinfunction "1_1") (pintype "passive"))
      (node (ref "R23") (pin "2") (pinfunction "2_2") (pintype "passive"))
      (node (ref "U2") (pin "2") (pinfunction "-IN_2") (pintype "input"))
    )
    (net (code "69") (name "Net-(U2-OUT)") (class "Default")
      (node (ref "R19") (pin "2") (pinfunction "2_2") (pintype "passive"))
      (node (ref "R25") (pin "1") (pinfunction "1_1") (pintype "passive"))
      (node (ref "R30") (pin "1") (pinfunction "1_1") (pintype "passive"))
      (node (ref "U2") (pin "6") (pinfunction "OUT_6") (pintype "output"))
    )
    (net (code "70") (name "Net-(U3--IN)") (class "Default")
      (node (ref "C3") (pin "2") (pinfunction "2_2") (pintype "passive"))
      (node (ref "R17") (pin "1") (pinfunction "1_1") (pintype "passive"))
      (node (ref "R18") (pin "1") (pinfunction "1_1") (pintype "passive"))
      (node (ref "U3") (pin "2") (pinfunction "-IN_2") (pintype "input"))
    )
    (net (code "71") (name "Net-(U4-+IN)") (class "Default")
      (node (ref "C5") (pin "2") (pinfunction "2_2") (pintype "passive"))
      (node (ref "R26") (pin "2") (pinfunction "2_2") (pintype "passive"))
      (node (ref "U4") (pin "3") (pinfunction "+IN_3") (pintype "input"))
    )
    (net (code "72") (name "Net-(U4--IN)") (class "Default")
      (node (ref "C2") (pin "1") (pinfunction "1_1") (pintype "passive"))
      (node (ref "R28") (pin "1") (pinfunction "1_1") (pintype "passive"))
      (node (ref "U4") (pin "2") (pinfunction "-IN_2") (pintype "input"))
      (node (ref "U4") (pin "6") (pinfunction "OUT_6") (pintype "output"))
    )
    (net (code "73") (name "Net-(U5-OUT)") (class "Default")
      (node (ref "R31") (pin "2") (pinfunction "2_2") (pintype "passive"))
      (node (ref "U5") (pin "6") (pinfunction "OUT_6") (pintype "output"))
      (node (ref "U6") (pin "3") (pinfunction "+IN_3") (pintype "input"))
    )
    (net (code "74") (name "Net-(U6--IN)") (class "Default")
      (node (ref "JP1") (pin "1") (pinfunction "1_1") (pintype "passive"))
      (node (ref "R35") (pin "2") (pinfunction "2_2") (pintype "passive"))
      (node (ref "R36") (pin "1") (pinfunction "1_1") (pintype "passive"))
      (node (ref "R37") (pin "2") (pinfunction "2_2") (pintype "passive"))
      (node (ref "R38") (pin "2") (pinfunction "2_2") (pintype "passive"))
      (node (ref "R39") (pin "2") (pinfunction "2_2") (pintype "passive"))
      (node (ref "R40") (pin "2") (pinfunction "2_2") (pintype "passive"))
      (node (ref "R41") (pin "2") (pinfunction "2_2") (pintype "passive"))
      (node (ref "R42") (pin "2") (pinfunction "2_2") (pintype "passive"))
      (node (ref "R43") (pin "2") (pinfunction "2_2") (pintype "passive"))
      (node (ref "R44") (pin "2") (pinfunction "2_2") (pintype "passive"))
      (node (ref "U6") (pin "2") (pinfunction "-IN_2") (pintype "input"))
    )
    (net (code "75") (name "Net-(U7-DRAIN0)") (class "Default")
      (node (ref "R40") (pin "1") (pinfunction "1_1") (pintype "passive"))
      (node (ref "U7") (pin "3") (pinfunction "DRAIN0_3") (pintype "bidirectional"))
    )
    (net (code "76") (name "Net-(U7-DRAIN1)") (class "Default")
      (node (ref "R39") (pin "1") (pinfunction "1_1") (pintype "passive"))
      (node (ref "U7") (pin "4") (pinfunction "DRAIN1_4") (pintype "bidirectional"))
    )
    (net (code "77") (name "Net-(U7-DRAIN2)") (class "Default")
      (node (ref "R38") (pin "1") (pinfunction "1_1") (pintype "passive"))
      (node (ref "U7") (pin "5") (pinfunction "DRAIN2_5") (pintype "bidirectional"))
    )
    (net (code "78") (name "Net-(U7-DRAIN3)") (class "Default")
      (node (ref "R37") (pin "1") (pinfunction "1_1") (pintype "passive"))
      (node (ref "U7") (pin "6") (pinfunction "DRAIN3_6") (pintype "bidirectional"))
    )
    (net (code "79") (name "Net-(U7-DRAIN4)") (class "Default")
      (node (ref "R44") (pin "1") (pinfunction "1_1") (pintype "passive"))
      (node (ref "U7") (pin "11") (pinfunction "DRAIN4_11") (pintype "bidirectional"))
    )
    (net (code "80") (name "Net-(U7-DRAIN5)") (class "Default")
      (node (ref "R43") (pin "1") (pinfunction "1_1") (pintype "passive"))
      (node (ref "U7") (pin "12") (pinfunction "DRAIN5_12") (pintype "bidirectional"))
    )
    (net (code "81") (name "Net-(U7-DRAIN6)") (class "Default")
      (node (ref "R42") (pin "1") (pinfunction "1_1") (pintype "passive"))
      (node (ref "U7") (pin "13") (pinfunction "DRAIN6_13") (pintype "bidirectional"))
    )
    (net (code "82") (name "Net-(U7-DRAIN7)") (class "Default")
      (node (ref "R41") (pin "1") (pinfunction "1_1") (pintype "passive"))
      (node (ref "U7") (pin "14") (pinfunction "DRAIN7_14") (pintype "bidirectional"))
    )
    (net (code "83") (name "Net-(U7-SCL)") (class "Default")
      (node (ref "R68") (pin "1") (pinfunction "1_1") (pintype "passive"))
      (node (ref "U7") (pin "15") (pinfunction "SCL_15") (pintype "bidirectional"))
    )
    (net (code "84") (name "Net-(U7-SDA)") (class "Default")
      (node (ref "R67") (pin "1") (pinfunction "1_1") (pintype "passive"))
      (node (ref "U7") (pin "2") (pinfunction "SDA_2") (pintype "bidirectional"))
    )
    (net (code "85") (name "Net-(U17-BST)") (class "Default")
      (node (ref "C20") (pin "2") (pinfunction "2_2") (pintype "passive"))
      (node (ref "U17") (pin "6") (pinfunction "BST_6") (pintype "bidirectional"))
    )
    (net (code "86") (name "Net-(U17-SW)") (class "Default")
      (node (ref "C20") (pin "1") (pinfunction "1_1") (pintype "passive"))
      (node (ref "L1") (pin "1") (pinfunction "1_1") (pintype "bidirectional"))
      (node (ref "U17") (pin "5") (pinfunction "SW_5") (pintype "bidirectional"))
    )
    (net (code "87") (name "SCL") (class "Default")
      (node (ref "IC1") (pin "12") (pinfunction "SCL_12") (pintype "input"))
      (node (ref "J2") (pin "3") (pinfunction "3_3") (pintype "passive"))
      (node (ref "R53") (pin "1") (pinfunction "1_1") (pintype "passive"))
      (node (ref "R68") (pin "2") (pinfunction "2_2") (pintype "passive"))
    )
    (net (code "88") (name "SDA") (class "Default")
      (node (ref "IC1") (pin "13") (pinfunction "SDA_13") (pintype "bidirectional"))
      (node (ref "J2") (pin "2") (pinfunction "2_2") (pintype "passive"))
      (node (ref "R54") (pin "1") (pinfunction "1_1") (pintype "passive"))
      (node (ref "R67") (pin "2") (pinfunction "2_2") (pintype "passive"))
    )
    (net (code "89") (name "V+") (class "Default")
      (node (ref "C63") (pin "2") (pinfunction "2_2") (pintype "passive"))
      (node (ref "C64") (pin "2") (pinfunction "2_2") (pintype "passive"))
      (node (ref "J5") (pin "1") (pinfunction "1_1") (pintype "passive"))
      (node (ref "R52") (pin "1") (pinfunction "1_1") (pintype "passive"))
      (node (ref "U17") (pin "2") (pinfunction "EN_2") (pintype "bidirectional"))
      (node (ref "U17") (pin "3") (pinfunction "VIN_3") (pintype "bidirectional"))
    )
    (net (code "90") (name "unconnected-(IC1-GPA3-Pad24)") (class "Default")
      (node (ref "IC1") (pin "24") (pinfunction "GPA3_24") (pintype "bidirectional"))
    )
    (net (code "91") (name "unconnected-(IC1-GPA4-Pad25)") (class "Default")
      (node (ref "IC1") (pin "25") (pinfunction "GPA4_25") (pintype "bidirectional"))
    )
    (net (code "92") (name "unconnected-(IC1-GPA6-Pad27)") (class "Default")
      (node (ref "IC1") (pin "27") (pinfunction "GPA6_27") (pintype "bidirectional"))
    )
    (net (code "93") (name "unconnected-(IC1-GPA7-Pad28)") (class "Default")
      (node (ref "IC1") (pin "28") (pinfunction "GPA7_28") (pintype "bidirectional"))
    )
    (net (code "94") (name "unconnected-(IC1-GPB0-Pad1)") (class "Default")
      (node (ref "IC1") (pin "1") (pinfunction "GPB0_1") (pintype "bidirectional"))
    )
    (net (code "95") (name "unconnected-(IC1-GPB1-Pad2)") (class "Default")
      (node (ref "IC1") (pin "2") (pinfunction "GPB1_2") (pintype "bidirectional"))
    )
    (net (code "96") (name "unconnected-(IC1-GPB6-Pad7)") (class "Default")
      (node (ref "IC1") (pin "7") (pinfunction "GPB6_7") (pintype "bidirectional"))
    )
    (net (code "97") (name "unconnected-(IC1-GPB7-Pad8)") (class "Default")
      (node (ref "IC1") (pin "8") (pinfunction "GPB7_8") (pintype "bidirectional"))
    )
    (net (code "98") (name "unconnected-(IC1-INTA-Pad20)") (class "Default")
      (node (ref "IC1") (pin "20") (pinfunction "INTA_20") (pintype "output"))
    )
    (net (code "99") (name "unconnected-(IC1-INTB-Pad19)") (class "Default")
      (node (ref "IC1") (pin "19") (pinfunction "INTB_19") (pintype "output"))
    )
    (net (code "100") (name "unconnected-(J2-Pad5)") (class "Default")
      (node (ref "J2") (pin "5") (pinfunction "5_5") (pintype "passive"))
    )
    (net (code "101") (name "unconnected-(MACHINE1-Pad2)") (class "Default")
      (node (ref "MACHINE1") (pin "2") (pinfunction "2_2") (pintype "passive"))
    )
    (net (code "102") (name "unconnected-(MACHINE1-Pad3)") (class "Default")
      (node (ref "MACHINE1") (pin "3") (pinfunction "3_3") (pintype "passive"))
    )
    (net (code "103") (name "unconnected-(MACHINE3-Pad2)") (class "Default")
      (node (ref "MACHINE3") (pin "2") (pinfunction "2_2") (pintype "passive"))
    )
    (net (code "104") (name "unconnected-(MACHINE3-Pad3)") (class "Default")
      (node (ref "MACHINE3") (pin "3") (pinfunction "3_3") (pintype "passive"))
    )
    (net (code "105") (name "unconnected-(U8-Pad3V3_EN)") (class "Default")
      (node (ref "U8") (pin "3V3_EN") (pinfunction "3V3_EN_3V3_EN") (pintype "bidirectional"))
    )
    (net (code "106") (name "unconnected-(U8-PadADC_VREF)") (class "Default")
      (node (ref "U8") (pin "ADC_VREF") (pinfunction "ADC_VREF_ADC_VREF") (pintype "bidirectional"))
    )
    (net (code "107") (name "unconnected-(U8-PadGP0)") (class "Default")
      (node (ref "U8") (pin "GP0") (pinfunction "GP0_GP0") (pintype "bidirectional"))
    )
    (net (code "108") (name "unconnected-(U8-PadGP1)") (class "Default")
      (node (ref "U8") (pin "GP1") (pinfunction "GP1_GP1") (pintype "bidirectional"))
    )
    (net (code "109") (name "unconnected-(U8-PadGP6)") (class "Default")
      (node (ref "U8") (pin "GP6") (pinfunction "GP6_GP6") (pintype "bidirectional"))
    )
    (net (code "110") (name "unconnected-(U8-PadGP7)") (class "Default")
      (node (ref "U8") (pin "GP7") (pinfunction "GP7_GP7") (pintype "bidirectional"))
    )
    (net (code "111") (name "unconnected-(U8-PadGP8)") (class "Default")
      (node (ref "U8") (pin "GP8") (pinfunction "GP8_GP8") (pintype "bidirectional"))
    )
    (net (code "112") (name "unconnected-(U8-PadGP9)") (class "Default")
      (node (ref "U8") (pin "GP9") (pinfunction "GP9_GP9") (pintype "bidirectional"))
    )
    (net (code "113") (name "unconnected-(U8-PadGP12)") (class "Default")
      (node (ref "U8") (pin "GP12") (pinfunction "GP12_GP12") (pintype "bidirectional"))
    )
    (net (code "114") (name "unconnected-(U8-PadGP13)") (class "Default")
      (node (ref "U8") (pin "GP13") (pinfunction "GP13_GP13") (pintype "bidirectional"))
    )
    (net (code "115") (name "unconnected-(U8-PadGP21)") (class "Default")
      (node (ref "U8") (pin "GP21") (pinfunction "GP21_GP21") (pintype "bidirectional"))
    )
    (net (code "116") (name "unconnected-(U8-PadRUN)") (class "Default")
      (node (ref "U8") (pin "RUN") (pinfunction "RUN_RUN") (pintype "bidirectional"))
    )
    (net (code "117") (name "unconnected-(U8-PadVBUS)") (class "Default")
      (node (ref "U8") (pin "VBUS") (pinfunction "VBUS_VBUS") (pintype "bidirectional"))
    )
    (net (code "118") (name "unconnected-(U8-PadVSYS)") (class "Default")
      (node (ref "U8") (pin "VSYS") (pinfunction "VSYS_VSYS") (pintype "bidirectional"))
    )
  )
)
